# OverCurrent_Protection.net
KiCad netlist of a schematic drawn in Altium Designer
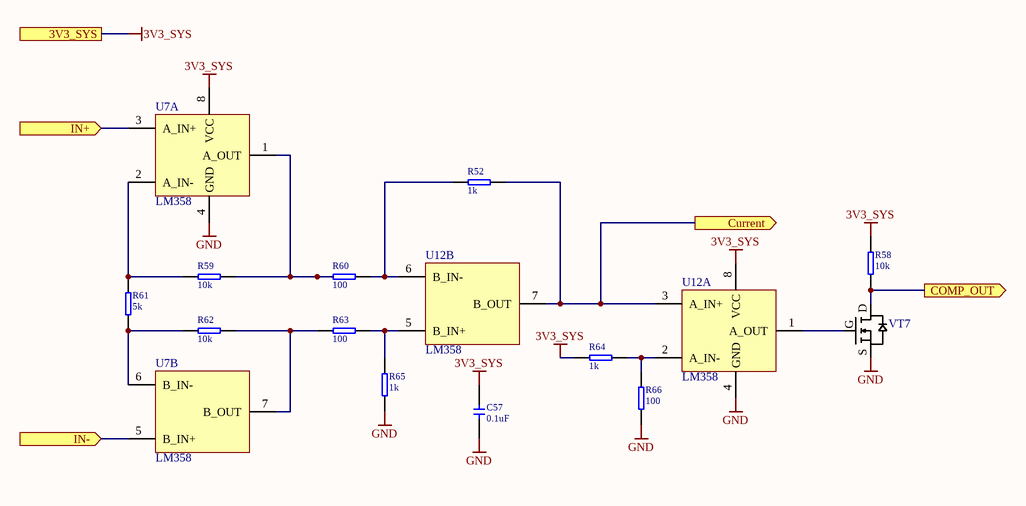
[diagram p0: OverCurrent_Protection.SchDoc]

(export (version "E")
  (design (tool "Eeschema 10.0.6"))
  (components
    (comp (ref "C57")
      (value "0.1uF")
      (footprint "CERCAP 0402")
      (description "Capacitor")
      (fields (field (name "VOLTAGE") "50V") (field (name "Comment") "CERCAP 0402 0.1uF 50V X7R"))
      (libsource (lib "!main") (part "!Capacitor"))
    )
    (comp (ref "R52")
      (value "1k")
      (footprint "RES 0402")
      (description "Resistor")
      (fields (field (name "Comment") "RES 0402 1k"))
      (libsource (lib "!main") (part "!Resistor"))
    )
    (comp (ref "R58")
      (value "10k")
      (footprint "RES 0402")
      (description "Resistor")
      (fields (field (name "Comment") "RES 0402 10k"))
      (libsource (lib "!main") (part "!Resistor"))
    )
    (comp (ref "R59")
      (value "10k")
      (footprint "RES 0402")
      (description "Resistor")
      (fields (field (name "Comment") "RES 0402 10k"))
      (libsource (lib "!main") (part "!Resistor"))
    )
    (comp (ref "R60")
      (value "100")
      (footprint "RES 0402")
      (description "Resistor")
      (fields (field (name "Comment") "RES 0402 100"))
      (libsource (lib "!main") (part "!Resistor"))
    )
    (comp (ref "R61")
      (value "5k")
      (footprint "RES 0402")
      (description "Resistor")
      (fields (field (name "Comment") "RES 0402 5k"))
      (libsource (lib "!main") (part "!Resistor"))
    )
    (comp (ref "R62")
      (value "10k")
      (footprint "RES 0402")
      (description "Resistor")
      (fields (field (name "Comment") "RES 0402 10k"))
      (libsource (lib "!main") (part "!Resistor"))
    )
    (comp (ref "R63")
      (value "100")
      (footprint "RES 0402")
      (description "Resistor")
      (fields (field (name "Comment") "RES 0402 100"))
      (libsource (lib "!main") (part "!Resistor"))
    )
    (comp (ref "R64")
      (value "1k")
      (footprint "RES 0402")
      (description "Resistor")
      (fields (field (name "Comment") "RES 0402 1k"))
      (libsource (lib "!main") (part "!Resistor"))
    )
    (comp (ref "R65")
      (value "1k")
      (footprint "RES 0402")
      (description "Resistor")
      (fields (field (name "Comment") "RES 0402 1k"))
      (libsource (lib "!main") (part "!Resistor"))
    )
    (comp (ref "R66")
      (value "100")
      (footprint "RES 0402")
      (description "Resistor")
      (fields (field (name "Comment") "RES 0402 100"))
      (libsource (lib "!main") (part "!Resistor"))
    )
    (comp (ref "U7")
      (value "LM358")
      (footprint "DFN-8-2x2")
      (description "Operational amplifier")
      (libsource (lib "analog") (part "DualOpAmp"))
    )
    (comp (ref "U12")
      (value "LM358")
      (footprint "DFN-8-2x2")
      (description "Operational amplifier")
      (libsource (lib "") (part "DualOpAmp_1"))
    )
    (comp (ref "VT7")
      (value "2N7002")
      (footprint "SOT23-3")
      (description "generic N mosfet")
      (libsource (lib "transistors") (part "!Generic N MOSFET"))
    )
  )
  (nets
    (net (code "1") (name "/COMP_OUT") (class "Default")
      (node (ref "R58") (pin "1") (pinfunction "11_1") (pintype "passive"))
      (node (ref "VT7") (pin "D6") (pintype "passive"))
    )
    (net (code "2") (name "/Current") (class "Default")
      (node (ref "R52") (pin "1") (pinfunction "11_1") (pintype "passive"))
      (node (ref "U12") (pin "3") (pinfunction "A_IN+_3") (pintype "passive"))
      (node (ref "U12") (pin "7") (pinfunction "B_OUT_7") (pintype "passive"))
    )
    (net (code "3") (name "/IN+") (class "Default")
      (node (ref "U7") (pin "3") (pinfunction "A_IN+_3") (pintype "passive"))
    )
    (net (code "4") (name "/IN-") (class "Default")
      (node (ref "U7") (pin "5") (pinfunction "B_IN+_5") (pintype "passive"))
    )
    (net (code "5") (name "3V3_SYS") (class "Default")
      (node (ref "C57") (pin "2") (pintype "passive"))
      (node (ref "R58") (pin "2") (pinfunction "12_2") (pintype "passive"))
      (node (ref "R64") (pin "2") (pinfunction "12_2") (pintype "passive"))
      (node (ref "U12") (pin "8") (pinfunction "VCC_8") (pintype "passive"))
      (node (ref "U7") (pin "8") (pinfunction "VCC_8") (pintype "passive"))
    )
    (net (code "6") (name "GND") (class "Default")
      (node (ref "C57") (pin "1") (pintype "passive"))
      (node (ref "R65") (pin "1") (pinfunction "11_1") (pintype "passive"))
      (node (ref "R66") (pin "2") (pinfunction "12_2") (pintype "passive"))
      (node (ref "U12") (pin "4") (pinfunction "GND_4") (pintype "passive"))
      (node (ref "U7") (pin "4") (pinfunction "GND_4") (pintype "passive"))
      (node (ref "VT7") (pin "S1") (pintype "passive"))
    )
    (net (code "7") (name "Net-(R52-12)") (class "Default")
      (node (ref "R52") (pin "2") (pinfunction "12_2") (pintype "passive"))
      (node (ref "R60") (pin "2") (pinfunction "12_2") (pintype "passive"))
      (node (ref "U12") (pin "6") (pinfunction "B_IN-_6") (pintype "passive"))
    )
    (net (code "8") (name "Net-(R59-11)") (class "Default")
      (node (ref "R59") (pin "1") (pinfunction "11_1") (pintype "passive"))
      (node (ref "R61") (pin "2") (pinfunction "12_2") (pintype "passive"))
      (node (ref "U7") (pin "2") (pinfunction "A_IN-_2") (pintype "passive"))
    )
    (net (code "9") (name "Net-(R59-12)") (class "Default")
      (node (ref "R59") (pin "2") (pinfunction "12_2") (pintype "passive"))
      (node (ref "R60") (pin "1") (pinfunction "11_1") (pintype "passive"))
      (node (ref "U7") (pin "1") (pinfunction "A_OUT_1") (pintype "passive"))
    )
    (net (code "10") (name "Net-(R61-11)") (class "Default")
      (node (ref "R61") (pin "1") (pinfunction "11_1") (pintype "passive"))
      (node (ref "R62") (pin "1") (pinfunction "11_1") (pintype "passive"))
      (node (ref "U7") (pin "6") (pinfunction "B_IN-_6") (pintype "passive"))
    )
    (net (code "11") (name "Net-(R62-12)") (class "Default")
      (node (ref "R62") (pin "2") (pinfunction "12_2") (pintype "passive"))
      (node (ref "R63") (pin "1") (pinfunction "11_1") (pintype "passive"))
      (node (ref "U7") (pin "7") (pinfunction "B_OUT_7") (pintype "passive"))
    )
    (net (code "12") (name "Net-(R63-12)") (class "Default")
      (node (ref "R63") (pin "2") (pinfunction "12_2") (pintype "passive"))
      (node (ref "R65") (pin "2") (pinfunction "12_2") (pintype "passive"))
      (node (ref "U12") (pin "5") (pinfunction "B_IN+_5") (pintype "passive"))
    )
    (net (code "13") (name "Net-(R64-11)") (class "Default")
      (node (ref "R64") (pin "1") (pinfunction "11_1") (pintype "passive"))
      (node (ref "R66") (pin "1") (pinfunction "11_1") (pintype "passive"))
      (node (ref "U12") (pin "2") (pinfunction "A_IN-_2") (pintype "passive"))
    )
    (net (code "14") (name "Net-(U12A-A_OUT)") (class "Default")
      (node (ref "U12") (pin "1") (pinfunction "A_OUT_1") (pintype "passive"))
      (node (ref "VT7") (pin "G2") (pintype "passive"))
    )
  )
)
